# textdisplay.net
KiCad netlist of a schematic drawn in EAGLE
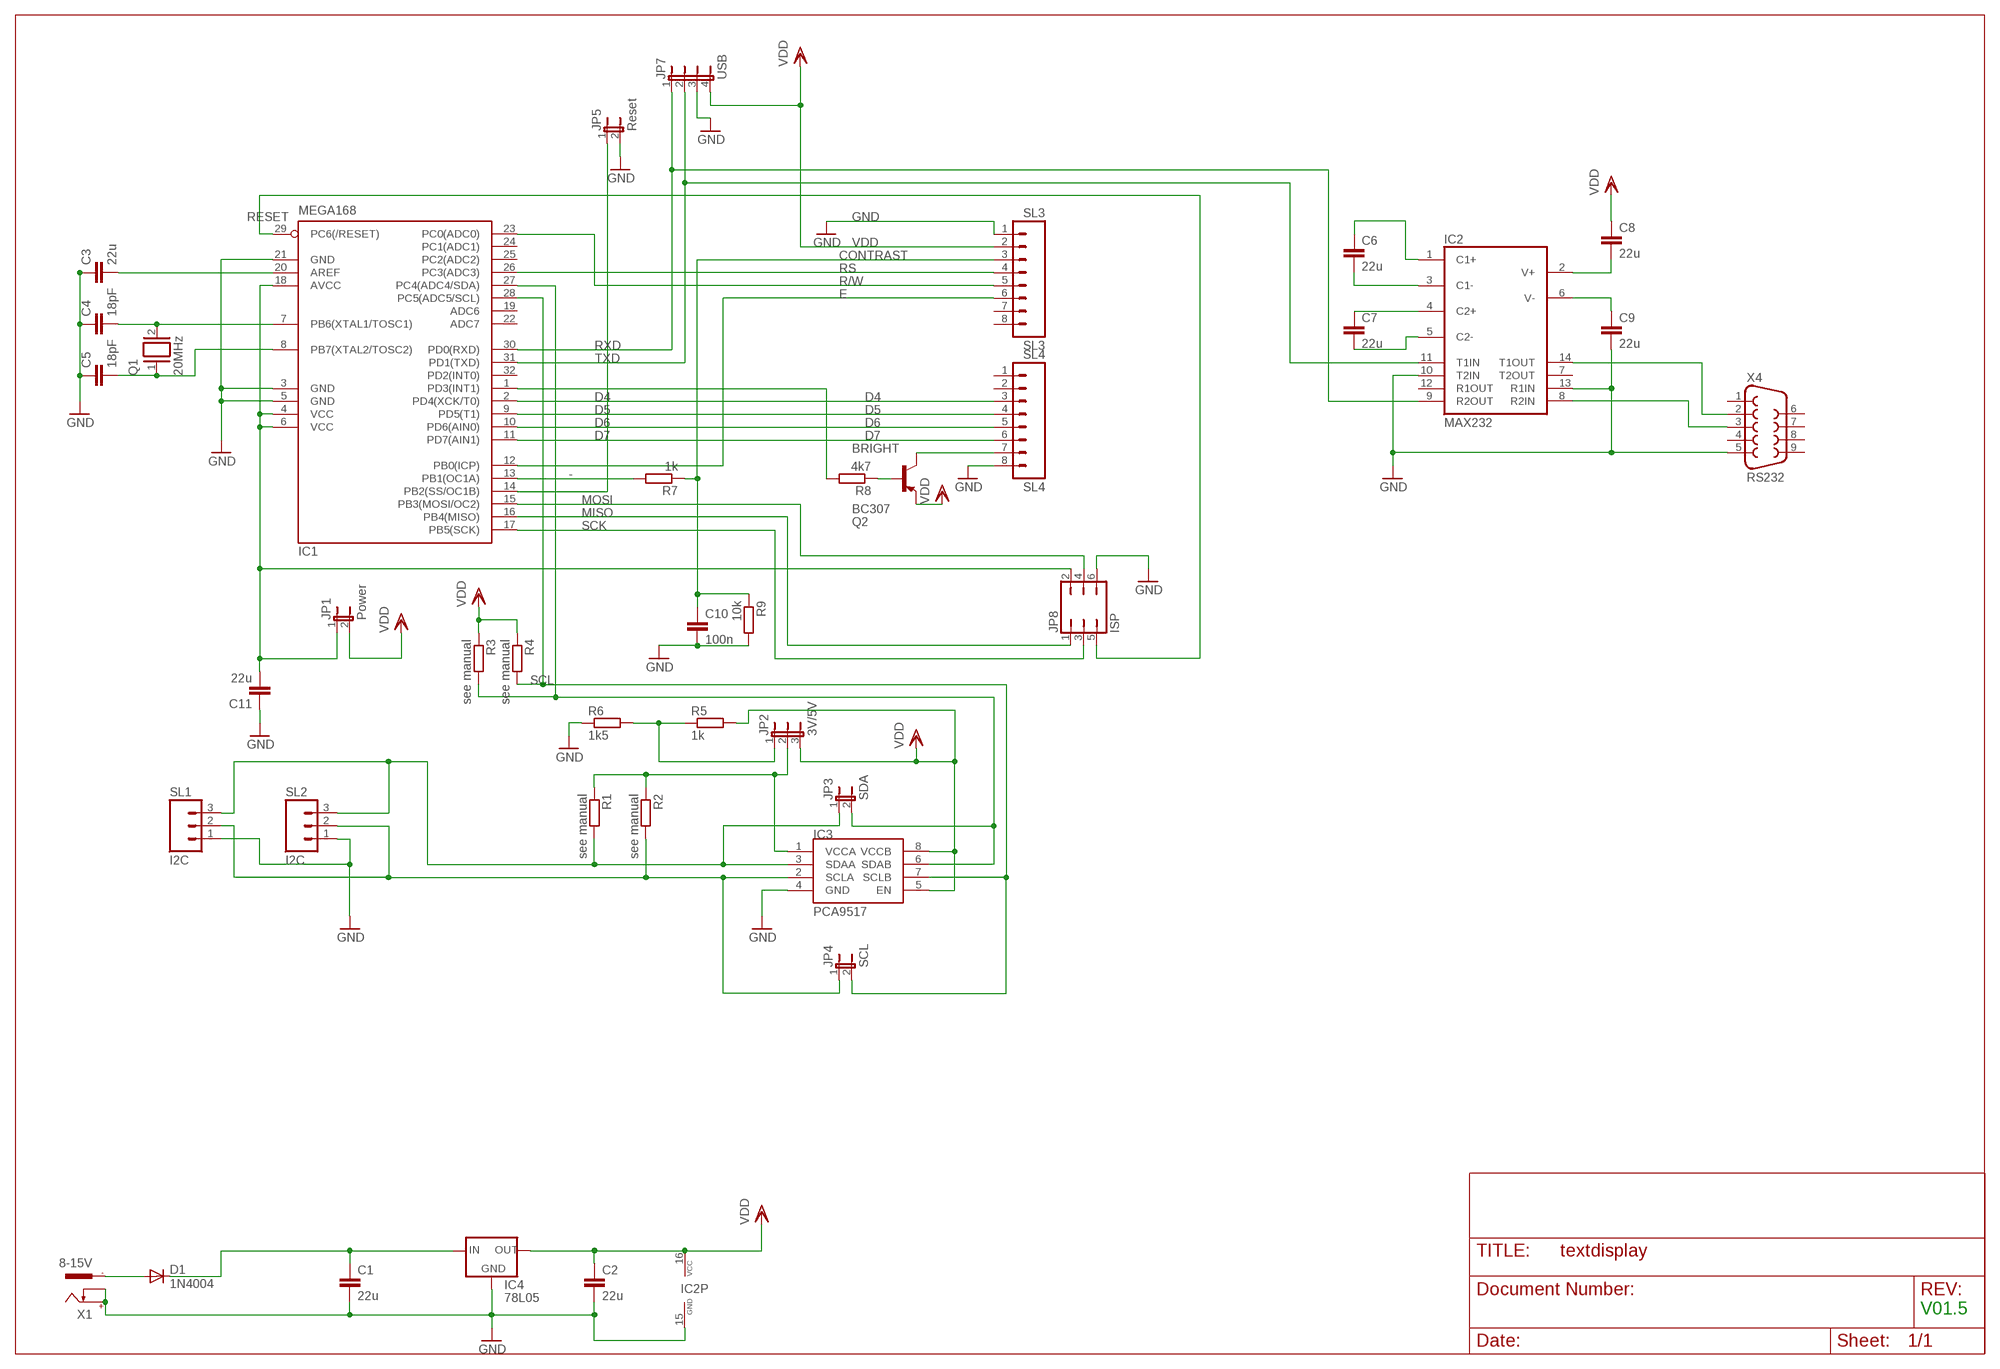
[diagram p0: schematic, sheet 1]

(export (version "E")
  (design (tool "Eeschema 10.0.6"))
  (components
    (comp (ref "C1")
      (value "22u")
      (footprint "eagle-import:C1206")
      (libsource (lib "eagle-import") (part "C-EUC1206"))
    )
    (comp (ref "C2")
      (value "22u")
      (footprint "eagle-import:C1206")
      (libsource (lib "eagle-import") (part "C-EUC1206"))
    )
    (comp (ref "C3")
      (value "22u")
      (footprint "eagle-import:C1206")
      (libsource (lib "eagle-import") (part "C-EUC1206"))
    )
    (comp (ref "C4")
      (value "18pF")
      (footprint "eagle-import:C025-025X050")
      (libsource (lib "eagle-import") (part "C-EU025-025X050"))
    )
    (comp (ref "C5")
      (value "18pF")
      (footprint "eagle-import:C025-025X050")
      (libsource (lib "eagle-import") (part "C-EU025-025X050"))
    )
    (comp (ref "C6")
      (value "22u")
      (footprint "eagle-import:C1206")
      (libsource (lib "eagle-import") (part "C-EUC1206"))
    )
    (comp (ref "C7")
      (value "22u")
      (footprint "eagle-import:C1206")
      (libsource (lib "eagle-import") (part "C-EUC1206"))
    )
    (comp (ref "C8")
      (value "22u")
      (footprint "eagle-import:C1206")
      (libsource (lib "eagle-import") (part "C-EUC1206"))
    )
    (comp (ref "C9")
      (value "22u")
      (footprint "eagle-import:C1206")
      (libsource (lib "eagle-import") (part "C-EUC1206"))
    )
    (comp (ref "C10")
      (value "100n")
      (footprint "eagle-import:C050-025X075")
      (libsource (lib "eagle-import") (part "C-EU050-025X075"))
    )
    (comp (ref "C11")
      (value "22u")
      (footprint "eagle-import:C1206")
      (libsource (lib "eagle-import") (part "C-EUC1206"))
    )
    (comp (ref "D1")
      (value "1N4004")
      (footprint "eagle-import:DO41-10")
      (libsource (lib "eagle-import") (part "1N4004"))
    )
    (comp (ref "IC1")
      (value "MEGA168")
      (footprint "eagle-import:TQFP32-08")
      (fields (field (name "MPN") "ATMEGA8-16AU"))
      (libsource (lib "eagle-import") (part "MEGA8-AI"))
    )
    (comp (ref "IC2")
      (value "MAX232")
      (footprint "eagle-import:DIL16")
      (fields (field (name "MF") "MAXIM") (field (name "MPN") "MAX232ACPE+"))
      (libsource (lib "eagle-import") (part "MAX232"))
    )
    (comp (ref "IC3")
      (value "PCA9517")
      (footprint "eagle-import:SO-08")
      (libsource (lib "eagle-import") (part "PCA9517"))
    )
    (comp (ref "IC4")
      (value "78L05")
      (footprint "eagle-import:78LXX")
      (libsource (lib "eagle-import") (part "78LXX"))
    )
    (comp (ref "JP1")
      (value "Power")
      (footprint "eagle-import:JP1")
      (libsource (lib "eagle-import") (part "JP1E"))
    )
    (comp (ref "JP2")
      (value "3V/5V")
      (footprint "eagle-import:JP2")
      (libsource (lib "eagle-import") (part "JP2E"))
    )
    (comp (ref "JP3")
      (value "SDA")
      (footprint "eagle-import:JP1")
      (libsource (lib "eagle-import") (part "JP1E"))
    )
    (comp (ref "JP4")
      (value "SCL")
      (footprint "eagle-import:JP1")
      (libsource (lib "eagle-import") (part "JP1E"))
    )
    (comp (ref "JP5")
      (value "Reset")
      (footprint "eagle-import:JP1")
      (libsource (lib "eagle-import") (part "JP1E"))
    )
    (comp (ref "JP7")
      (value "USB")
      (footprint "eagle-import:JP4")
      (libsource (lib "eagle-import") (part "JP4E"))
    )
    (comp (ref "JP8")
      (value "ISP")
      (footprint "eagle-import:JP3Q")
      (libsource (lib "eagle-import") (part "JP3Q"))
    )
    (comp (ref "Q1")
      (value "20MHz")
      (footprint "eagle-import:QS")
      (libsource (lib "eagle-import") (part "XTAL/S"))
    )
    (comp (ref "Q2")
      (value "BC307")
      (footprint "eagle-import:TO92")
      (libsource (lib "eagle-import") (part "BC307"))
    )
    (comp (ref "R1")
      (value "see manual")
      (footprint "eagle-import:R1206")
      (libsource (lib "eagle-import") (part "R-EU_R1206"))
    )
    (comp (ref "R2")
      (value "see manual")
      (footprint "eagle-import:R1206")
      (libsource (lib "eagle-import") (part "R-EU_R1206"))
    )
    (comp (ref "R3")
      (value "see manual")
      (footprint "eagle-import:R1206")
      (libsource (lib "eagle-import") (part "R-EU_R1206"))
    )
    (comp (ref "R4")
      (value "see manual")
      (footprint "eagle-import:R1206")
      (libsource (lib "eagle-import") (part "R-EU_R1206"))
    )
    (comp (ref "R5")
      (value "1k")
      (footprint "eagle-import:R1206")
      (libsource (lib "eagle-import") (part "R-EU_R1206"))
    )
    (comp (ref "R6")
      (value "1k5")
      (footprint "eagle-import:R1206")
      (libsource (lib "eagle-import") (part "R-EU_R1206"))
    )
    (comp (ref "R7")
      (value "1k")
      (footprint "eagle-import:R1206")
      (libsource (lib "eagle-import") (part "R-EU_R1206"))
    )
    (comp (ref "R8")
      (value "4k7")
      (footprint "eagle-import:R1206")
      (libsource (lib "eagle-import") (part "R-EU_R1206"))
    )
    (comp (ref "R9")
      (value "10k")
      (footprint "eagle-import:R1206")
      (libsource (lib "eagle-import") (part "R-EU_R1206"))
    )
    (comp (ref "SL1")
      (value "I2C")
      (footprint "eagle-import:03P")
      (libsource (lib "eagle-import") (part "M03"))
    )
    (comp (ref "SL2")
      (value "I2C")
      (footprint "eagle-import:03P")
      (libsource (lib "eagle-import") (part "M03"))
    )
    (comp (ref "SL3")
      (value "SL3")
      (footprint "eagle-import:08P")
      (libsource (lib "eagle-import") (part "M08"))
    )
    (comp (ref "SL4")
      (value "SL4")
      (footprint "eagle-import:08P")
      (libsource (lib "eagle-import") (part "M08"))
    )
    (comp (ref "X1")
      (value "8-15V")
      (footprint "eagle-import:737992-5")
      (libsource (lib "eagle-import") (part "737992-55"))
    )
    (comp (ref "X4")
      (value "RS232")
      (footprint "eagle-import:F09H")
      (libsource (lib "eagle-import") (part "F09H"))
    )
  )
  (nets
    (net (code "1") (name "/-") (class "Default")
      (node (ref "IC1") (pin "13") (pinfunction "PB1(OC1A)_13") (pintype "bidirectional"))
      (node (ref "R7") (pin "2") (pinfunction "2_2") (pintype "passive"))
    )
    (net (code "2") (name "/BRIGHT") (class "Default")
      (node (ref "Q2") (pin "3") (pinfunction "C_3") (pintype "passive"))
      (node (ref "SL4") (pin "7") (pinfunction "7_7") (pintype "passive"))
    )
    (net (code "3") (name "/CONTRAST") (class "Default")
      (node (ref "C10") (pin "1") (pinfunction "1_1") (pintype "passive"))
      (node (ref "R7") (pin "1") (pinfunction "1_1") (pintype "passive"))
      (node (ref "R9") (pin "1") (pinfunction "1_1") (pintype "passive"))
      (node (ref "SL3") (pin "3") (pinfunction "3_3") (pintype "passive"))
    )
    (net (code "4") (name "/D4") (class "Default")
      (node (ref "IC1") (pin "2") (pinfunction "PD4(XCK/T0)_2") (pintype "bidirectional"))
      (node (ref "SL4") (pin "3") (pinfunction "3_3") (pintype "passive"))
    )
    (net (code "5") (name "/D5") (class "Default")
      (node (ref "IC1") (pin "9") (pinfunction "PD5(T1)_9") (pintype "bidirectional"))
      (node (ref "SL4") (pin "4") (pinfunction "4_4") (pintype "passive"))
    )
    (net (code "6") (name "/D6") (class "Default")
      (node (ref "IC1") (pin "10") (pinfunction "PD6(AIN0)_10") (pintype "bidirectional"))
      (node (ref "SL4") (pin "5") (pinfunction "5_5") (pintype "passive"))
    )
    (net (code "7") (name "/D7") (class "Default")
      (node (ref "IC1") (pin "11") (pinfunction "PD7(AIN1)_11") (pintype "bidirectional"))
      (node (ref "SL4") (pin "6") (pinfunction "6_6") (pintype "passive"))
    )
    (net (code "8") (name "/E") (class "Default")
      (node (ref "IC1") (pin "12") (pinfunction "PB0(ICP)_12") (pintype "bidirectional"))
      (node (ref "SL3") (pin "6") (pinfunction "6_6") (pintype "passive"))
    )
    (net (code "9") (name "/MISO") (class "Default")
      (node (ref "IC1") (pin "16") (pinfunction "PB4(MISO)_16") (pintype "bidirectional"))
      (node (ref "JP8") (pin "1") (pinfunction "1_1") (pintype "passive"))
    )
    (net (code "10") (name "/MOSI") (class "Default")
      (node (ref "IC1") (pin "15") (pinfunction "PB3(MOSI/OC2)_15") (pintype "bidirectional"))
      (node (ref "JP8") (pin "4") (pinfunction "4_4") (pintype "passive"))
    )
    (net (code "11") (name "/RESET") (class "Default")
      (node (ref "IC1") (pin "29") (pinfunction "PC6(/RESET)_29") (pintype "bidirectional"))
      (node (ref "JP8") (pin "5") (pinfunction "5_5") (pintype "passive"))
    )
    (net (code "12") (name "/RS") (class "Default")
      (node (ref "IC1") (pin "26") (pinfunction "PC3(ADC3)_26") (pintype "bidirectional"))
      (node (ref "SL3") (pin "4") (pinfunction "4_4") (pintype "passive"))
    )
    (net (code "13") (name "/RXD") (class "Default")
      (node (ref "IC1") (pin "30") (pinfunction "PD0(RXD)_30") (pintype "bidirectional"))
      (node (ref "IC2") (pin "9") (pinfunction "R2OUT_9") (pintype "output"))
      (node (ref "JP7") (pin "1") (pinfunction "1_1") (pintype "passive"))
    )
    (net (code "14") (name "/R{slash}W") (class "Default")
      (node (ref "IC1") (pin "23") (pinfunction "PC0(ADC0)_23") (pintype "bidirectional"))
      (node (ref "SL3") (pin "5") (pinfunction "5_5") (pintype "passive"))
    )
    (net (code "15") (name "/SCK") (class "Default")
      (node (ref "IC1") (pin "17") (pinfunction "PB5(SCK)_17") (pintype "bidirectional"))
      (node (ref "JP8") (pin "3") (pinfunction "3_3") (pintype "passive"))
    )
    (net (code "16") (name "/SCL") (class "Default")
      (node (ref "IC1") (pin "28") (pinfunction "PC5(ADC5/SCL)_28") (pintype "bidirectional"))
      (node (ref "IC3") (pin "7") (pinfunction "SCLB_7") (pintype "bidirectional"))
      (node (ref "JP4") (pin "2") (pinfunction "2_2") (pintype "passive"))
      (node (ref "R4") (pin "2") (pinfunction "2_2") (pintype "passive"))
    )
    (net (code "17") (name "/TXD") (class "Default")
      (node (ref "IC1") (pin "31") (pinfunction "PD1(TXD)_31") (pintype "bidirectional"))
      (node (ref "IC2") (pin "11") (pinfunction "T1IN_11") (pintype "input"))
      (node (ref "JP7") (pin "2") (pinfunction "2_2") (pintype "passive"))
    )
    (net (code "18") (name "GND") (class "Default")
      (node (ref "C1") (pin "2") (pinfunction "2_2") (pintype "passive"))
      (node (ref "C10") (pin "2") (pinfunction "2_2") (pintype "passive"))
      (node (ref "C11") (pin "1") (pinfunction "1_1") (pintype "passive"))
      (node (ref "C2") (pin "2") (pinfunction "2_2") (pintype "passive"))
      (node (ref "C3") (pin "1") (pinfunction "1_1") (pintype "passive"))
      (node (ref "C4") (pin "1") (pinfunction "1_1") (pintype "passive"))
      (node (ref "C5") (pin "1") (pinfunction "1_1") (pintype "passive"))
      (node (ref "C9") (pin "2") (pinfunction "2_2") (pintype "passive"))
      (node (ref "IC1") (pin "21") (pinfunction "GND_21") (pintype "power_in"))
      (node (ref "IC1") (pin "3") (pinfunction "GND_3") (pintype "power_in"))
      (node (ref "IC1") (pin "5") (pinfunction "GND_5") (pintype "power_in"))
      (node (ref "IC2") (pin "10") (pinfunction "T2IN_10") (pintype "input"))
      (node (ref "IC2") (pin "13") (pinfunction "R1IN_13") (pintype "input"))
      (node (ref "IC2") (pin "15") (pinfunction "GND_15") (pintype "power_in"))
      (node (ref "IC3") (pin "4") (pinfunction "GND_4") (pintype "bidirectional"))
      (node (ref "IC4") (pin "GND") (pinfunction "GND_GND") (pintype "input"))
      (node (ref "JP5") (pin "2") (pinfunction "2_2") (pintype "passive"))
      (node (ref "JP7") (pin "3") (pinfunction "3_3") (pintype "passive"))
      (node (ref "JP8") (pin "6") (pinfunction "6_6") (pintype "passive"))
      (node (ref "R6") (pin "1") (pinfunction "1_1") (pintype "passive"))
      (node (ref "R9") (pin "2") (pinfunction "2_2") (pintype "passive"))
      (node (ref "SL1") (pin "1") (pinfunction "1_1") (pintype "passive"))
      (node (ref "SL2") (pin "1") (pinfunction "1_1") (pintype "passive"))
      (node (ref "SL3") (pin "1") (pinfunction "1_1") (pintype "passive"))
      (node (ref "SL4") (pin "8") (pinfunction "8_8") (pintype "passive"))
      (node (ref "X1") (pin "+") (pinfunction "+_+") (pintype "passive"))
      (node (ref "X1") (pin "K") (pinfunction "K_K") (pintype "passive"))
      (node (ref "X4") (pin "5") (pinfunction "5_5") (pintype "passive"))
    )
    (net (code "19") (name "Net-(C1-Pad1)") (class "Default")
      (node (ref "C1") (pin "1") (pinfunction "1_1") (pintype "passive"))
      (node (ref "D1") (pin "C") (pinfunction "C_C") (pintype "passive"))
      (node (ref "IC4") (pin "IN") (pinfunction "IN_IN") (pintype "input"))
    )
    (net (code "20") (name "Net-(D1-PadA)") (class "Default")
      (node (ref "D1") (pin "A") (pinfunction "A_A") (pintype "passive"))
      (node (ref "X1") (pin "-1") (pinfunction "-1_-1") (pintype "passive"))
    )
    (net (code "21") (name "Net-(IC1-AREF)") (class "Default")
      (node (ref "C3") (pin "2") (pinfunction "2_2") (pintype "passive"))
      (node (ref "IC1") (pin "20") (pinfunction "AREF_20") (pintype "passive"))
    )
    (net (code "22") (name "Net-(IC1-AVCC)") (class "Default")
      (node (ref "C11") (pin "2") (pinfunction "2_2") (pintype "passive"))
      (node (ref "IC1") (pin "18") (pinfunction "AVCC_18") (pintype "power_in"))
      (node (ref "IC1") (pin "4") (pinfunction "VCC_4") (pintype "power_in"))
      (node (ref "IC1") (pin "6") (pinfunction "VCC_6") (pintype "power_in"))
      (node (ref "JP1") (pin "1") (pinfunction "1_1") (pintype "passive"))
      (node (ref "JP8") (pin "2") (pinfunction "2_2") (pintype "passive"))
    )
    (net (code "23") (name "Net-(IC1-PB2(SS{slash}OC1B))") (class "Default")
      (node (ref "IC1") (pin "14") (pinfunction "PB2(SS/OC1B)_14") (pintype "bidirectional"))
      (node (ref "JP5") (pin "1") (pinfunction "1_1") (pintype "passive"))
    )
    (net (code "24") (name "Net-(IC1-PB6(XTAL1{slash}TOSC1))") (class "Default")
      (node (ref "C4") (pin "2") (pinfunction "2_2") (pintype "passive"))
      (node (ref "IC1") (pin "7") (pinfunction "PB6(XTAL1/TOSC1)_7") (pintype "bidirectional"))
      (node (ref "Q1") (pin "2") (pinfunction "2_2") (pintype "passive"))
    )
    (net (code "25") (name "Net-(IC1-PB7(XTAL2{slash}TOSC2))") (class "Default")
      (node (ref "C5") (pin "2") (pinfunction "2_2") (pintype "passive"))
      (node (ref "IC1") (pin "8") (pinfunction "PB7(XTAL2/TOSC2)_8") (pintype "bidirectional"))
      (node (ref "Q1") (pin "1") (pinfunction "1_1") (pintype "passive"))
    )
    (net (code "26") (name "Net-(IC1-PC4(ADC4{slash}SDA))") (class "Default")
      (node (ref "IC1") (pin "27") (pinfunction "PC4(ADC4/SDA)_27") (pintype "bidirectional"))
      (node (ref "IC3") (pin "6") (pinfunction "SDAB_6") (pintype "bidirectional"))
      (node (ref "JP3") (pin "2") (pinfunction "2_2") (pintype "passive"))
      (node (ref "R3") (pin "2") (pinfunction "2_2") (pintype "passive"))
    )
    (net (code "27") (name "Net-(IC1-PD3(INT1))") (class "Default")
      (node (ref "IC1") (pin "1") (pinfunction "PD3(INT1)_1") (pintype "bidirectional"))
      (node (ref "R8") (pin "2") (pinfunction "2_2") (pintype "passive"))
    )
    (net (code "28") (name "Net-(IC2A-C1+)") (class "Default")
      (node (ref "C6") (pin "1") (pinfunction "1_1") (pintype "passive"))
      (node (ref "IC2") (pin "1") (pinfunction "C1+_1") (pintype "bidirectional"))
    )
    (net (code "29") (name "Net-(IC2A-C1-)") (class "Default")
      (node (ref "C6") (pin "2") (pinfunction "2_2") (pintype "passive"))
      (node (ref "IC2") (pin "3") (pinfunction "C1-_3") (pintype "bidirectional"))
    )
    (net (code "30") (name "Net-(IC2A-C2+)") (class "Default")
      (node (ref "C7") (pin "1") (pinfunction "1_1") (pintype "passive"))
      (node (ref "IC2") (pin "4") (pinfunction "C2+_4") (pintype "bidirectional"))
    )
    (net (code "31") (name "Net-(IC2A-C2-)") (class "Default")
      (node (ref "C7") (pin "2") (pinfunction "2_2") (pintype "passive"))
      (node (ref "IC2") (pin "5") (pinfunction "C2-_5") (pintype "bidirectional"))
    )
    (net (code "32") (name "Net-(IC2A-R2IN)") (class "Default")
      (node (ref "IC2") (pin "8") (pinfunction "R2IN_8") (pintype "input"))
      (node (ref "X4") (pin "3") (pinfunction "3_3") (pintype "passive"))
    )
    (net (code "33") (name "Net-(IC2A-T1OUT)") (class "Default")
      (node (ref "IC2") (pin "14") (pinfunction "T1OUT_14") (pintype "output"))
      (node (ref "X4") (pin "2") (pinfunction "2_2") (pintype "passive"))
    )
    (net (code "34") (name "Net-(IC2A-V+)") (class "Default")
      (node (ref "C8") (pin "2") (pinfunction "2_2") (pintype "passive"))
      (node (ref "IC2") (pin "2") (pinfunction "V+_2") (pintype "bidirectional"))
    )
    (net (code "35") (name "Net-(IC2A-V-)") (class "Default")
      (node (ref "C9") (pin "1") (pinfunction "1_1") (pintype "passive"))
      (node (ref "IC2") (pin "6") (pinfunction "V-_6") (pintype "bidirectional"))
    )
    (net (code "36") (name "Net-(IC3-SCLA)") (class "Default")
      (node (ref "IC3") (pin "2") (pinfunction "SCLA_2") (pintype "bidirectional"))
      (node (ref "JP4") (pin "1") (pinfunction "1_1") (pintype "passive"))
      (node (ref "R2") (pin "2") (pinfunction "2_2") (pintype "passive"))
      (node (ref "SL1") (pin "2") (pinfunction "2_2") (pintype "passive"))
      (node (ref "SL2") (pin "2") (pinfunction "2_2") (pintype "passive"))
    )
    (net (code "37") (name "Net-(IC3-SDAA)") (class "Default")
      (node (ref "IC3") (pin "3") (pinfunction "SDAA_3") (pintype "bidirectional"))
      (node (ref "JP3") (pin "1") (pinfunction "1_1") (pintype "passive"))
      (node (ref "R1") (pin "2") (pinfunction "2_2") (pintype "passive"))
      (node (ref "SL1") (pin "3") (pinfunction "3_3") (pintype "passive"))
      (node (ref "SL2") (pin "3") (pinfunction "3_3") (pintype "passive"))
    )
    (net (code "38") (name "Net-(IC3-VCCA)") (class "Default")
      (node (ref "IC3") (pin "1") (pinfunction "VCCA_1") (pintype "bidirectional"))
      (node (ref "JP2") (pin "2") (pinfunction "2_2") (pintype "passive"))
      (node (ref "R1") (pin "1") (pinfunction "1_1") (pintype "passive"))
      (node (ref "R2") (pin "1") (pinfunction "1_1") (pintype "passive"))
    )
    (net (code "39") (name "Net-(JP2-Pad1)") (class "Default")
      (node (ref "JP2") (pin "1") (pinfunction "1_1") (pintype "passive"))
      (node (ref "R5") (pin "1") (pinfunction "1_1") (pintype "passive"))
      (node (ref "R6") (pin "2") (pinfunction "2_2") (pintype "passive"))
    )
    (net (code "40") (name "Net-(Q2-B)") (class "Default")
      (node (ref "Q2") (pin "2") (pinfunction "B_2") (pintype "passive"))
      (node (ref "R8") (pin "1") (pinfunction "1_1") (pintype "passive"))
    )
    (net (code "41") (name "VDD") (class "Default")
      (node (ref "C2") (pin "1") (pinfunction "1_1") (pintype "passive"))
      (node (ref "C8") (pin "1") (pinfunction "1_1") (pintype "passive"))
      (node (ref "IC2") (pin "16") (pinfunction "VCC_16") (pintype "power_in"))
      (node (ref "IC3") (pin "5") (pinfunction "EN_5") (pintype "bidirectional"))
      (node (ref "IC3") (pin "8") (pinfunction "VCCB_8") (pintype "bidirectional"))
      (node (ref "IC4") (pin "OUT") (pinfunction "OUT_OUT") (pintype "passive"))
      (node (ref "JP1") (pin "2") (pinfunction "2_2") (pintype "passive"))
      (node (ref "JP2") (pin "3") (pinfunction "3_3") (pintype "passive"))
      (node (ref "JP7") (pin "4") (pinfunction "4_4") (pintype "passive"))
      (node (ref "Q2") (pin "1") (pinfunction "E_1") (pintype "passive"))
      (node (ref "R3") (pin "1") (pinfunction "1_1") (pintype "passive"))
      (node (ref "R4") (pin "1") (pinfunction "1_1") (pintype "passive"))
      (node (ref "R5") (pin "2") (pinfunction "2_2") (pintype "passive"))
      (node (ref "SL3") (pin "2") (pinfunction "2_2") (pintype "passive"))
    )
    (net (code "42") (name "unconnected-(IC1-ADC6-Pad19)") (class "Default")
      (node (ref "IC1") (pin "19") (pinfunction "ADC6_19") (pintype "bidirectional"))
    )
    (net (code "43") (name "unconnected-(IC1-ADC7-Pad22)") (class "Default")
      (node (ref "IC1") (pin "22") (pinfunction "ADC7_22") (pintype "bidirectional"))
    )
    (net (code "44") (name "unconnected-(IC1-PC1(ADC1)-Pad24)") (class "Default")
      (node (ref "IC1") (pin "24") (pinfunction "PC1(ADC1)_24") (pintype "bidirectional"))
    )
    (net (code "45") (name "unconnected-(IC1-PC2(ADC2)-Pad25)") (class "Default")
      (node (ref "IC1") (pin "25") (pinfunction "PC2(ADC2)_25") (pintype "bidirectional"))
    )
    (net (code "46") (name "unconnected-(IC1-PD2(INT0)-Pad32)") (class "Default")
      (node (ref "IC1") (pin "32") (pinfunction "PD2(INT0)_32") (pintype "bidirectional"))
    )
    (net (code "47") (name "unconnected-(IC2A-R1OUT-Pad12)") (class "Default")
      (node (ref "IC2") (pin "12") (pinfunction "R1OUT_12") (pintype "output"))
    )
    (net (code "48") (name "unconnected-(IC2A-T2OUT-Pad7)") (class "Default")
      (node (ref "IC2") (pin "7") (pinfunction "T2OUT_7") (pintype "output"))
    )
    (net (code "49") (name "unconnected-(SL3-Pad7)") (class "Default")
      (node (ref "SL3") (pin "7") (pinfunction "7_7") (pintype "passive"))
    )
    (net (code "50") (name "unconnected-(SL3-Pad8)") (class "Default")
      (node (ref "SL3") (pin "8") (pinfunction "8_8") (pintype "passive"))
    )
    (net (code "51") (name "unconnected-(SL4-Pad1)") (class "Default")
      (node (ref "SL4") (pin "1") (pinfunction "1_1") (pintype "passive"))
    )
    (net (code "52") (name "unconnected-(SL4-Pad2)") (class "Default")
      (node (ref "SL4") (pin "2") (pinfunction "2_2") (pintype "passive"))
    )
    (net (code "53") (name "unconnected-(X1-Pad-2)") (class "Default")
      (node (ref "X1") (pin "-2") (pinfunction "-2_-2") (pintype "passive"))
    )
    (net (code "54") (name "unconnected-(X4-Pad1)") (class "Default")
      (node (ref "X4") (pin "1") (pinfunction "1_1") (pintype "passive"))
    )
    (net (code "55") (name "unconnected-(X4-Pad4)") (class "Default")
      (node (ref "X4") (pin "4") (pinfunction "4_4") (pintype "passive"))
    )
    (net (code "56") (name "unconnected-(X4-Pad6)") (class "Default")
      (node (ref "X4") (pin "6") (pinfunction "6_6") (pintype "passive"))
    )
    (net (code "57") (name "unconnected-(X4-Pad7)") (class "Default")
      (node (ref "X4") (pin "7") (pinfunction "7_7") (pintype "passive"))
    )
    (net (code "58") (name "unconnected-(X4-Pad8)") (class "Default")
      (node (ref "X4") (pin "8") (pinfunction "8_8") (pintype "passive"))
    )
    (net (code "59") (name "unconnected-(X4-Pad9)") (class "Default")
      (node (ref "X4") (pin "9") (pinfunction "9_9") (pintype "passive"))
    )
  )
)
